# Power_Supply_and_Connector.net
KiCad netlist of a schematic drawn in Altium Designer
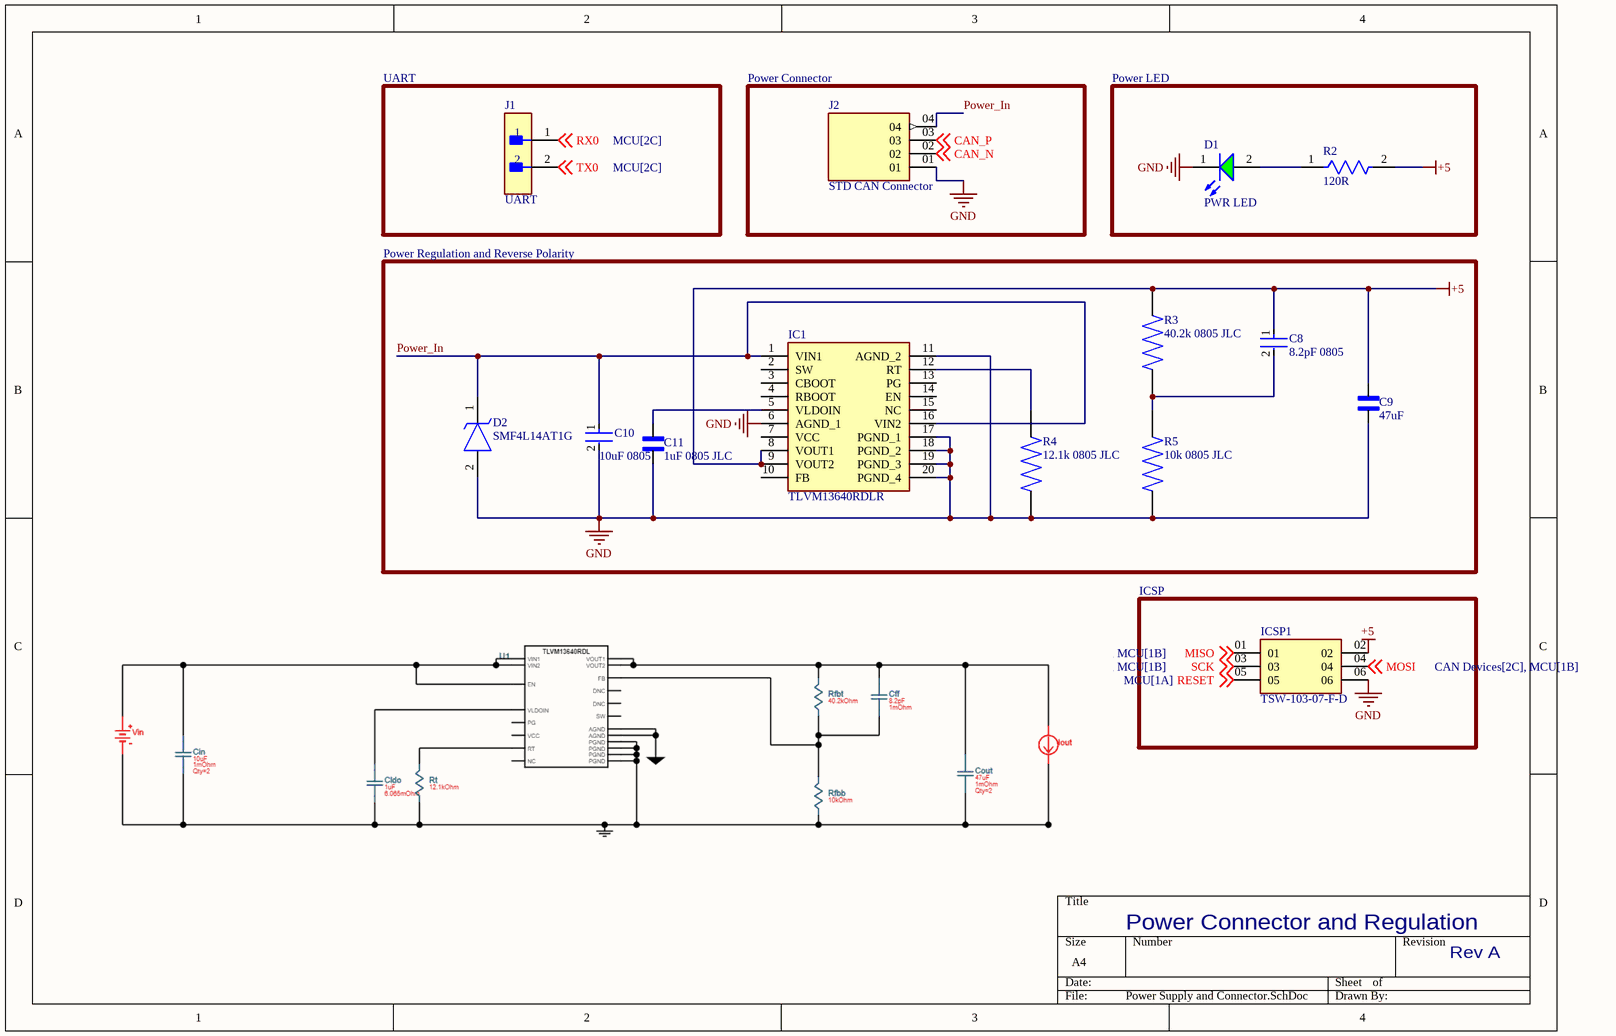
[diagram p0: Power Supply and Connector.SchDoc]

(export (version "E")
  (design (tool "Eeschema 10.0.6"))
  (components
    (comp (ref "C8")
      (value "8.2pF 0805")
      (footprint "FP-GQM219-0_15-IPC_C")
      (description "Ceramic Capacitor 8.2pF ±0.25pF 250VDC C0G 0805 Paper T/R")
      (libsource (lib "Altium Content Vault") (part "b4654b650e69147ec39a6b967a45e02"))
    )
    (comp (ref "C9")
      (value "47uF")
      (footprint "GRM31CR61E476ME44K:CAPC3216X160N")
      (fields
        (field (name "MF") "{'manufacturer': u'Murata Electronics'}")
        (field (name "MP") "GRM31CR61E476ME44K")
      )
      (libsource (lib "*") (part "GRM31CR61E476ME44K"))
    )
    (comp (ref "C10")
      (value "10uF 0805")
      (footprint "FP-GRM21B-0_2-e0_2_0_7-IPC_A")
      (description "Chip Multilayer Ceramic Capacitors for General Purpose, 0805, 10uF, X5R, 15%, 10%, 50V")
      (fields (field (name "TOLERANCE") "10%"))
      (libsource (lib "Altium Content Vault") (part "b4654b650e69147ec39a6b967a45e02"))
    )
    (comp (ref "C11")
      (value "1uF 0805 JLC")
      (footprint "CL21B105KBFNNNE:CAPC2012X140N")
      (description "Capacitor: ceramic; MLCC; 1uF; 50V; X7R; Â±10%; SMD; 0805")
      (fields
        (field (name "MF") "{'manufacturer': u'Samsung Electro-Mechanics'}")
        (field (name "MP") "CL21B105KBFNNNE")
      )
      (libsource (lib "*") (part "CL21B105KBFNNNE"))
    )
    (comp (ref "D1")
      (value "PWR LED")
      (footprint "WL-SMCW_0805_150080xx75000")
      (description "WURTH ELEKTRONIK - 150080GS75000 - LED, Green, SMD, 0805, 30 mA, 3.2 V, 520 nm")
      (libsource (lib "Altium Content Vault") (part "LED_Green_2A-1K"))
    )
    (comp (ref "D2")
      (value "SMF4L14AT1G")
      (footprint "SamacSys:SODFL3619X98N")
      (description "TVS Diode (Uni-directional)")
      (fields (field (name "MOUSER PART NUMBER") "576-SMF4L14AT1G"))
      (libsource (lib "*") (part "SMF4L14AT1G"))
    )
    (comp (ref "IC1")
      (value "TLVM13640RDLR")
      (footprint "SamacSys:TLVM13640RDLR")
      (description "Integrated Circuit")
      (fields (field (name "MOUSER PART NUMBER") "595-TLVM13640RDLR"))
      (libsource (lib "*") (part "TLVM13640RDLR"))
    )
    (comp (ref "ICSP1")
      (value "TSW-103-07-F-D")
      (footprint "TSW-103-07-F-D:SAMTEC_TSW-103-07-F-D")
      (fields (field (name "MF") "{'manufacturer': u'Samtec'}"))
      (libsource (lib "*") (part "TSW-103-07-F-D"))
    )
    (comp (ref "J1")
      (value "UART")
      (footprint "FP-TSW-102-07-F-S-MFG")
      (description "CONN HEADER VERT 2POS 2.54MM")
      (libsource (lib "Altium Content Vault") (part "3bc925449376181038e59eaffc5286c"))
    )
    (comp (ref "J2")
      (value "STD CAN Connector")
      (footprint "TSW-104-07-F-S:SAMTEC_TSW-104-07-F-S")
      (fields (field (name "MF") "{'manufacturer': u'Samtec'}") (field (name "MP") "TSW-104-07-F-S"))
      (libsource (lib "*") (part "TSW-104-07-F-S"))
    )
    (comp (ref "R2")
      (value "120R")
      (footprint "FP-CRCW0805-e3-IPC_C")
      (description "RES Thick Film, 120Ω, 1%, 0.125W, 100ppm/°C, 0805")
      (fields (field (name "TOLERANCE") "1%"))
      (libsource (lib "Altium Content Vault") (part "1029c3af85768c4190bb7ad29bc67b5"))
    )
    (comp (ref "R3")
      (value "40.2k 0805 JLC")
      (footprint "0805W8F4022T5E:RESC2012X65N")
      (fields (field (name "MF") "{'manufacturer': u'Uni-Royal'}") (field (name "MP") "0805W8F4022T5E"))
      (libsource (lib "*") (part "0805W8F4022T5E"))
    )
    (comp (ref "R4")
      (value "12.1k 0805 JLC")
      (footprint "0805W8F1212T5E:RESC2012X65N")
      (fields (field (name "MF") "{'manufacturer': u'Uni-Royal'}") (field (name "MP") "0805W8F1212T5E"))
      (libsource (lib "*") (part "0805W8F1212T5E"))
    )
    (comp (ref "R5")
      (value "10k 0805 JLC")
      (footprint "0805W8F1002T5E:RESC2012X65N")
      (fields (field (name "MF") "{'manufacturer': u'Uni-Royal'}") (field (name "MP") "0805W8F1002T5E"))
      (libsource (lib "*") (part "0805W8F1002T5E"))
    )
  )
  (nets
    (net (code "1") (name "+5") (class "Default")
      (node (ref "C8") (pin "1") (pinfunction "1_1") (pintype "passive"))
      (node (ref "C9") (pin "2") (pinfunction "2_2") (pintype "passive"))
      (node (ref "IC1") (pin "8") (pinfunction "VOUT1_8") (pintype "passive"))
      (node (ref "IC1") (pin "9") (pinfunction "VOUT2_9") (pintype "passive"))
      (node (ref "ICSP1") (pin "02") (pinfunction "02_02") (pintype "passive"))
      (node (ref "R2") (pin "2") (pinfunction "2_2") (pintype "passive"))
      (node (ref "R3") (pin "2") (pinfunction "2_2") (pintype "passive"))
    )
    (net (code "2") (name "/Power_In") (class "Default")
      (node (ref "C10") (pin "1") (pinfunction "1_1") (pintype "passive"))
      (node (ref "D2") (pin "1") (pinfunction "K_1") (pintype "passive"))
      (node (ref "IC1") (pin "1") (pinfunction "VIN1_1") (pintype "passive"))
      (node (ref "IC1") (pin "16") (pinfunction "VIN2_16") (pintype "passive"))
      (node (ref "J2") (pin "04") (pinfunction "04_04") (pintype "output"))
    )
    (net (code "3") (name "CAN_N") (class "Default")
      (node (ref "J2") (pin "02") (pinfunction "02_02") (pintype "passive"))
    )
    (net (code "4") (name "CAN_P") (class "Default")
      (node (ref "J2") (pin "03") (pinfunction "03_03") (pintype "passive"))
    )
    (net (code "5") (name "GND") (class "Default")
      (node (ref "C10") (pin "2") (pinfunction "2_2") (pintype "passive"))
      (node (ref "C11") (pin "2") (pinfunction "2_2") (pintype "passive"))
      (node (ref "C9") (pin "1") (pinfunction "1_1") (pintype "passive"))
      (node (ref "D1") (pin "1") (pinfunction "K_1") (pintype "passive"))
      (node (ref "D2") (pin "2") (pinfunction "A_2") (pintype "passive"))
      (node (ref "IC1") (pin "11") (pinfunction "AGND_2_11") (pintype "passive"))
      (node (ref "IC1") (pin "17") (pinfunction "PGND_1_17") (pintype "passive"))
      (node (ref "IC1") (pin "18") (pinfunction "PGND_2_18") (pintype "passive"))
      (node (ref "IC1") (pin "19") (pinfunction "PGND_3_19") (pintype "passive"))
      (node (ref "IC1") (pin "20") (pinfunction "PGND_4_20") (pintype "passive"))
      (node (ref "IC1") (pin "6") (pinfunction "AGND_1_6") (pintype "passive"))
      (node (ref "ICSP1") (pin "06") (pinfunction "06_06") (pintype "passive"))
      (node (ref "J2") (pin "01") (pinfunction "01_01") (pintype "passive"))
      (node (ref "R4") (pin "1") (pinfunction "1_1") (pintype "passive"))
      (node (ref "R5") (pin "1") (pinfunction "1_1") (pintype "passive"))
    )
    (net (code "6") (name "MISO") (class "Default")
      (node (ref "ICSP1") (pin "01") (pinfunction "01_01") (pintype "passive"))
    )
    (net (code "7") (name "MOSI") (class "Default")
      (node (ref "ICSP1") (pin "04") (pinfunction "04_04") (pintype "passive"))
    )
    (net (code "8") (name "Net-(C8-Pad2)") (class "Default")
      (node (ref "C8") (pin "2") (pinfunction "2_2") (pintype "passive"))
      (node (ref "R3") (pin "1") (pinfunction "1_1") (pintype "passive"))
      (node (ref "R5") (pin "2") (pinfunction "2_2") (pintype "passive"))
    )
    (net (code "9") (name "Net-(D1-A)") (class "Default")
      (node (ref "D1") (pin "2") (pinfunction "A_2") (pintype "passive"))
      (node (ref "R2") (pin "1") (pinfunction "1_1") (pintype "passive"))
    )
    (net (code "10") (name "Net-(IC1-RT)") (class "Default")
      (node (ref "IC1") (pin "12") (pinfunction "RT_12") (pintype "passive"))
      (node (ref "R4") (pin "2") (pinfunction "2_2") (pintype "passive"))
    )
    (net (code "11") (name "Net-(IC1-VLDOIN)") (class "Default")
      (node (ref "C11") (pin "1") (pinfunction "1_1") (pintype "passive"))
      (node (ref "IC1") (pin "5") (pinfunction "VLDOIN_5") (pintype "passive"))
    )
    (net (code "12") (name "RESET") (class "Default")
      (node (ref "ICSP1") (pin "05") (pinfunction "05_05") (pintype "passive"))
    )
    (net (code "13") (name "RX0") (class "Default")
      (node (ref "J1") (pin "1") (pinfunction "1_1") (pintype "passive"))
    )
    (net (code "14") (name "SCK") (class "Default")
      (node (ref "ICSP1") (pin "03") (pinfunction "03_03") (pintype "passive"))
    )
    (net (code "15") (name "TX0") (class "Default")
      (node (ref "J1") (pin "2") (pinfunction "2_2") (pintype "passive"))
    )
    (net (code "16") (name "unconnected-(IC1-CBOOT-Pad3)") (class "Default")
      (node (ref "IC1") (pin "3") (pinfunction "CBOOT_3") (pintype "passive"))
    )
    (net (code "17") (name "unconnected-(IC1-EN-Pad14)") (class "Default")
      (node (ref "IC1") (pin "14") (pinfunction "EN_14") (pintype "passive"))
    )
    (net (code "18") (name "unconnected-(IC1-FB-Pad10)") (class "Default")
      (node (ref "IC1") (pin "10") (pinfunction "FB_10") (pintype "passive"))
    )
    (net (code "19") (name "unconnected-(IC1-NC-Pad15)") (class "Default")
      (node (ref "IC1") (pin "15") (pinfunction "NC_15") (pintype "passive"))
    )
    (net (code "20") (name "unconnected-(IC1-PG-Pad13)") (class "Default")
      (node (ref "IC1") (pin "13") (pinfunction "PG_13") (pintype "passive"))
    )
    (net (code "21") (name "unconnected-(IC1-RBOOT-Pad4)") (class "Default")
      (node (ref "IC1") (pin "4") (pinfunction "RBOOT_4") (pintype "passive"))
    )
    (net (code "22") (name "unconnected-(IC1-SW-Pad2)") (class "Default")
      (node (ref "IC1") (pin "2") (pinfunction "SW_2") (pintype "passive"))
    )
    (net (code "23") (name "unconnected-(IC1-VCC-Pad7)") (class "Default")
      (node (ref "IC1") (pin "7") (pinfunction "VCC_7") (pintype "passive"))
    )
  )
)
